# 1-Controller.net
KiCad netlist of a schematic drawn in Altium Designer
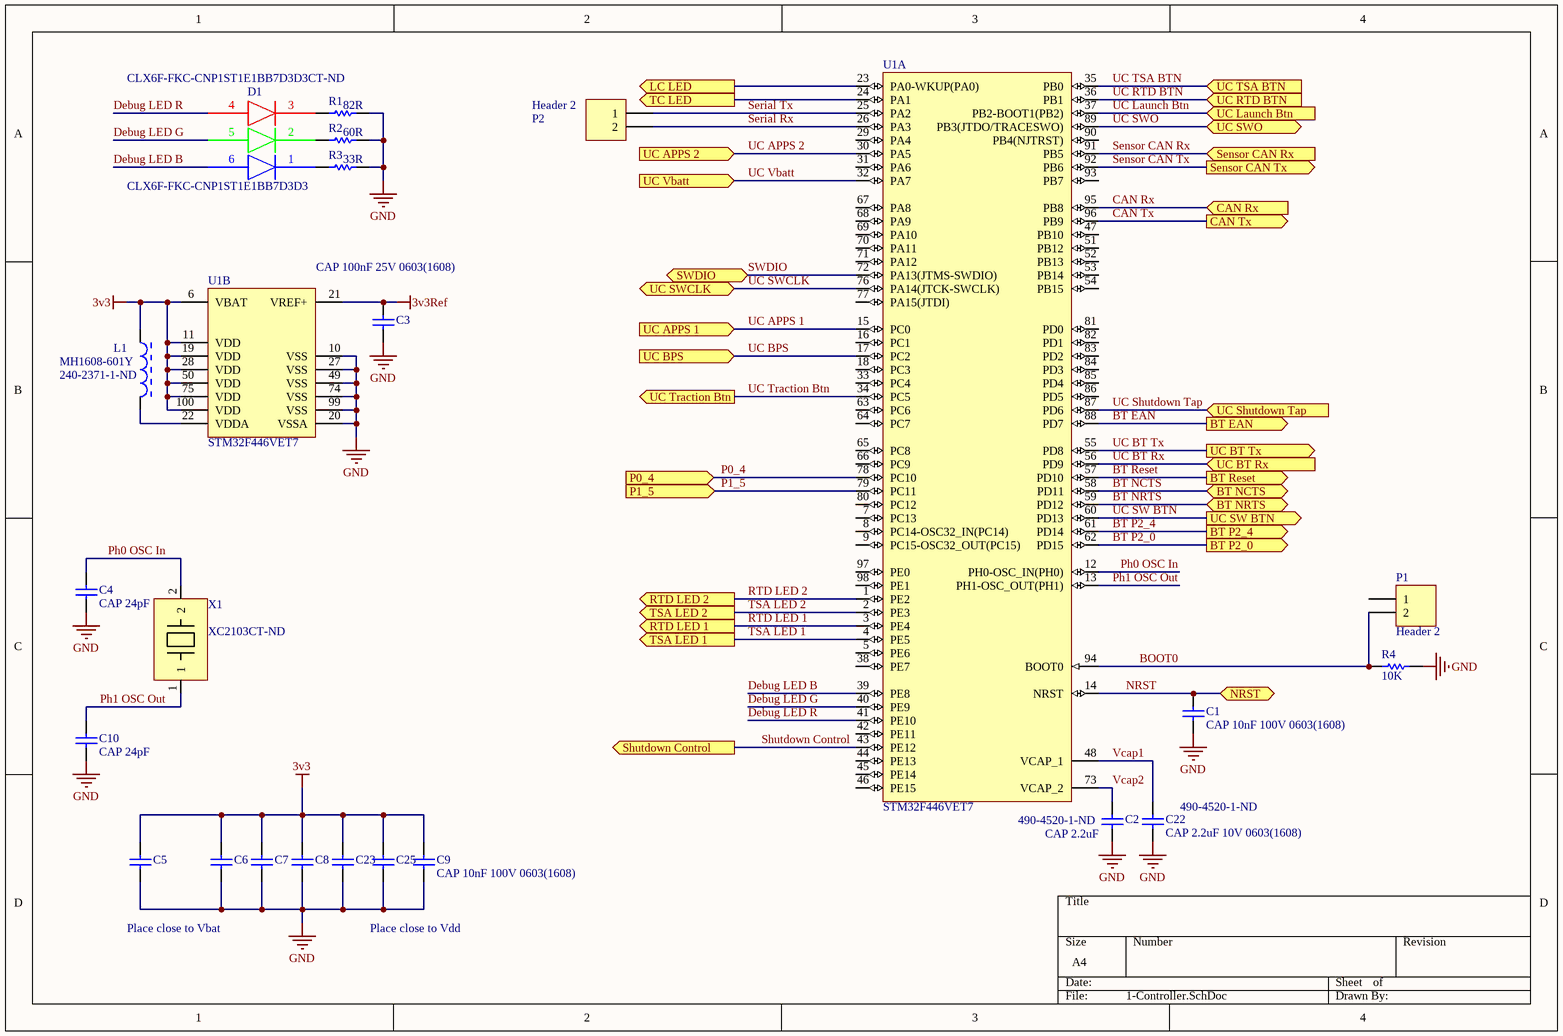
[diagram p0: 1-Controller.SchDoc]

(export (version "E")
  (design (tool "Eeschema 10.0.6"))
  (components
    (comp (ref "C1")
      (value "CAP 10nF 100V 0603(1608)")
      (footprint "CAPC0603(1608)100_M")
      (description "CAP 10nF 100V ±20% 0603 (1608 Metric) Thickness 1mm SMD")
      (fields (field (name "TOLERANCE") "Â±20%"))
      (libsource (lib "Altium Content Vault") (part "CAP"))
    )
    (comp (ref "C2")
      (value "CAP 2.2uF")
      (footprint "CAPC0603(1608)55_N")
      (description "CAP 2.2uF 10V ±10% 0603 (1608 Metric) Thickness 0.55mm SMD")
      (fields (field (name "TOLERANCE") "Â±10%") (field (name "SUPPLIER PART NUMBER 1") "490-4520-1-ND"))
      (libsource (lib "Altium Content Vault") (part "CAP"))
    )
    (comp (ref "C3")
      (value "CAP 100nF 25V 0603(1608)")
      (footprint "CAPC0603(1608)100_N")
      (description "CAP 100nF 25V ±20% 0603 (1608 Metric) Thickness 1mm SMD")
      (fields (field (name "TOLERANCE") "Â±20%"))
      (libsource (lib "Altium Content Vault") (part "CAP"))
    )
    (comp (ref "C4")
      (value "CAP 24pF")
      (footprint "CAPC0603(1608)100_N")
      (description "CAP 24pF 16V ±2% 0603 (1608 Metric) Thickness 1mm SMD")
      (fields (field (name "TOLERANCE") "Â±2%"))
      (libsource (lib "Altium Content Vault") (part "CAP"))
    )
    (comp (ref "C5")
      (value "CAP 10nF 100V 0603(1608)")
      (footprint "CAPC0603(1608)100_M")
      (description "CAP 10nF 100V ±20% 0603 (1608 Metric) Thickness 1mm SMD")
      (fields (field (name "TOLERANCE") "Â±20%"))
      (libsource (lib "Altium Content Vault") (part "CAP"))
    )
    (comp (ref "C6")
      (value "CAP 10nF 100V 0603(1608)")
      (footprint "CAPC0603(1608)100_M")
      (description "CAP 10nF 100V ±20% 0603 (1608 Metric) Thickness 1mm SMD")
      (fields (field (name "TOLERANCE") "Â±20%"))
      (libsource (lib "Altium Content Vault") (part "CAP"))
    )
    (comp (ref "C7")
      (value "CAP 10nF 100V 0603(1608)")
      (footprint "CAPC0603(1608)100_M")
      (description "CAP 10nF 100V ±20% 0603 (1608 Metric) Thickness 1mm SMD")
      (fields (field (name "TOLERANCE") "Â±20%"))
      (libsource (lib "Altium Content Vault") (part "CAP"))
    )
    (comp (ref "C8")
      (value "CAP 10nF 100V 0603(1608)")
      (footprint "CAPC0603(1608)100_M")
      (description "CAP 10nF 100V ±20% 0603 (1608 Metric) Thickness 1mm SMD")
      (fields (field (name "TOLERANCE") "Â±20%"))
      (libsource (lib "Altium Content Vault") (part "CAP"))
    )
    (comp (ref "C9")
      (value "CAP 10nF 100V 0603(1608)")
      (footprint "CAPC0603(1608)100_M")
      (description "CAP 10nF 100V ±20% 0603 (1608 Metric) Thickness 1mm SMD")
      (fields (field (name "TOLERANCE") "Â±20%"))
      (libsource (lib "Altium Content Vault") (part "CAP"))
    )
    (comp (ref "C10")
      (value "CAP 24pF")
      (footprint "CAPC0603(1608)100_N")
      (description "CAP 24pF 16V ±2% 0603 (1608 Metric) Thickness 1mm SMD")
      (fields (field (name "TOLERANCE") "Â±2%"))
      (libsource (lib "Altium Content Vault") (part "CAP"))
    )
    (comp (ref "C22")
      (value "CAP 2.2uF 10V 0603(1608)")
      (footprint "CAPC0603(1608)55_N")
      (description "CAP 2.2uF 10V ±10% 0603 (1608 Metric) Thickness 0.55mm SMD")
      (fields (field (name "TOLERANCE") "Â±10%") (field (name "SUPPLIER PART NUMBER 1") "490-4520-1-ND"))
      (libsource (lib "Altium Content Vault") (part "CAP"))
    )
    (comp (ref "C23")
      (value "CAP 10nF 100V 0603(1608)")
      (footprint "CAPC0603(1608)100_M")
      (description "CAP 10nF 100V ±20% 0603 (1608 Metric) Thickness 1mm SMD")
      (fields (field (name "TOLERANCE") "Â±20%"))
      (libsource (lib "Altium Content Vault") (part "CAP"))
    )
    (comp (ref "C25")
      (value "CAP 10nF 100V 0603(1608)")
      (footprint "CAPC0603(1608)100_M")
      (description "CAP 10nF 100V ±20% 0603 (1608 Metric) Thickness 1mm SMD")
      (fields (field (name "TOLERANCE") "Â±20%"))
      (libsource (lib "Altium Content Vault") (part "CAP"))
    )
    (comp (ref "D1")
      (value "CLX6F-FKC-CNP1ST1E1BB7D3D3")
      (footprint "CLX6C-FKB")
      (fields (field (name "SUPPLIER PART NUMBER 1") "CLX6F-FKC-CNP1ST1E1BB7D3D3CT-ND"))
      (libsource (lib "VCB_2019") (part "LED - CLX6F-FKC-CNP1ST1E1BB7D3D3"))
    )
    (comp (ref "L1")
      (value "MH1608-601Y")
      (footprint "BOUR-MH1608_V")
      (description "Chip Bead, 600 Ohm, 1 A, -55 to 125 degC, 2-Pin SMD (0603), RoHS, Tape and Reel")
      (fields (field (name "MANUFACTURER") "Bourns") (field (name "SUPPLIER PART NUMBER 1") "240-2371-1-ND"))
      (libsource (lib "Altium Content Vault") (part "IND-FB-2"))
    )
    (comp (ref "P1")
      (value "Header 2")
      (footprint "HDR1X2")
      (description "Header, 2-Pin")
      (fields (field (name "PUBLISHER") "Altium Limited"))
      (libsource (lib "") (part "Header 2_1"))
    )
    (comp (ref "P2")
      (value "Header 2")
      (footprint "HDR1X2")
      (description "Header, 2-Pin")
      (fields (field (name "PUBLISHER") "Altium Limited"))
      (libsource (lib "Miscellaneous Connectors") (part "Header 2"))
    )
    (comp (ref "R1")
      (value "82R")
      (footprint "RESC0603(1608)_N")
      (description "82R 0.1W 5% 0603 (1608 Metric)  SMD")
      (fields (field (name "TOLERANCE") "5 %") (field (name "POWER") "0.1 W"))
      (libsource (lib "Altium Content Vault") (part "RES"))
    )
    (comp (ref "R2")
      (value "60R")
      (footprint "RESC0603(1608)_N")
      (description "60R4 0.1W 1% 0603 (1608 Metric)  SMD")
      (fields (field (name "TOLERANCE") "1 %") (field (name "POWER") "0.1 W"))
      (libsource (lib "Altium Content Vault") (part "RES"))
    )
    (comp (ref "R3")
      (value "33R")
      (footprint "RESC0603(1608)_N")
      (description "33R 0.1W 5% 0603 (1608 Metric)  SMD")
      (fields (field (name "TOLERANCE") "5 %") (field (name "POWER") "0.1 W"))
      (libsource (lib "Altium Content Vault") (part "RES"))
    )
    (comp (ref "R4")
      (value "10K")
      (footprint "RESC0603(1608)_N")
      (description "10K 0.1W 5% 0603 (1608 Metric)  SMD")
      (fields (field (name "TOLERANCE") "5 %") (field (name "POWER") "0.1 W"))
      (libsource (lib "Altium Content Vault") (part "RES"))
    )
    (comp (ref "U1")
      (value "STM32F446VET7")
      (footprint "STM-LQFP100_L")
      (libsource (lib "Altium Content Vault") (part "MC-ARM-STM32F446-LQFP100"))
    )
    (comp (ref "X1")
      (value "7A-8.000MAAJ-T")
      (footprint "2-SMD, No Lead")
      (fields
        (field (name "MANUFACTURER") "TXC CORPORATION")
        (field (name "SUPPLIER PART NUMBER 1") "XC2103CT-ND")
      )
      (libsource (lib "VCU Library") (part "8MHz crystal, 7A-8.000MAAJ-T"))
    )
  )
  (nets
    (net (code "1") (name "/BOOT0") (class "Default")
      (node (ref "P1") (pin "2") (pinfunction "2_2") (pintype "passive"))
      (node (ref "R4") (pin "1") (pinfunction "1_1") (pintype "passive"))
      (node (ref "U1") (pin "94") (pinfunction "BOOT0_94") (pintype "input"))
    )
    (net (code "2") (name "/BT EAN") (class "Default")
      (node (ref "U1") (pin "88") (pinfunction "PD7_88") (pintype "bidirectional"))
    )
    (net (code "3") (name "/BT NCTS") (class "Default")
      (node (ref "U1") (pin "58") (pinfunction "PD11_58") (pintype "bidirectional"))
    )
    (net (code "4") (name "/BT NRTS") (class "Default")
      (node (ref "U1") (pin "59") (pinfunction "PD12_59") (pintype "bidirectional"))
    )
    (net (code "5") (name "/BT P2_0") (class "Default")
      (node (ref "U1") (pin "62") (pinfunction "PD15_62") (pintype "bidirectional"))
    )
    (net (code "6") (name "/BT P2_4") (class "Default")
      (node (ref "U1") (pin "61") (pinfunction "PD14_61") (pintype "bidirectional"))
    )
    (net (code "7") (name "/BT Reset") (class "Default")
      (node (ref "U1") (pin "57") (pinfunction "PD10_57") (pintype "bidirectional"))
    )
    (net (code "8") (name "/CAN Rx") (class "Default")
      (node (ref "U1") (pin "95") (pinfunction "PB8_95") (pintype "bidirectional"))
    )
    (net (code "9") (name "/CAN Tx") (class "Default")
      (node (ref "U1") (pin "96") (pinfunction "PB9_96") (pintype "bidirectional"))
    )
    (net (code "10") (name "/Debug LED B") (class "Default")
      (node (ref "D1") (pin "6") (pinfunction "B_6") (pintype "passive"))
      (node (ref "U1") (pin "39") (pinfunction "PE8_39") (pintype "bidirectional"))
    )
    (net (code "11") (name "/Debug LED G") (class "Default")
      (node (ref "D1") (pin "5") (pinfunction "G_5") (pintype "passive"))
      (node (ref "U1") (pin "40") (pinfunction "PE9_40") (pintype "bidirectional"))
    )
    (net (code "12") (name "/Debug LED R") (class "Default")
      (node (ref "D1") (pin "4") (pinfunction "R_4") (pintype "passive"))
      (node (ref "U1") (pin "41") (pinfunction "PE10_41") (pintype "bidirectional"))
    )
    (net (code "13") (name "/LC LED") (class "Default")
      (node (ref "U1") (pin "23") (pinfunction "PA0-WKUP(PA0)_23") (pintype "bidirectional"))
    )
    (net (code "14") (name "/NRST") (class "Default")
      (node (ref "C1") (pin "2") (pinfunction "2_2") (pintype "passive"))
      (node (ref "U1") (pin "14") (pinfunction "NRST_14") (pintype "bidirectional"))
    )
    (net (code "15") (name "/P0_4") (class "Default")
      (node (ref "U1") (pin "78") (pinfunction "PC10_78") (pintype "bidirectional"))
    )
    (net (code "16") (name "/P1_5") (class "Default")
      (node (ref "U1") (pin "79") (pinfunction "PC11_79") (pintype "bidirectional"))
    )
    (net (code "17") (name "/Ph0 OSC In") (class "Default")
      (node (ref "C4") (pin "2") (pinfunction "2_2") (pintype "passive"))
      (node (ref "U1") (pin "12") (pinfunction "PH0-OSC_IN(PH0)_12") (pintype "bidirectional"))
      (node (ref "X1") (pin "2") (pinfunction "2_2") (pintype "passive"))
    )
    (net (code "18") (name "/Ph1 OSC Out") (class "Default")
      (node (ref "C10") (pin "2") (pinfunction "2_2") (pintype "passive"))
      (node (ref "U1") (pin "13") (pinfunction "PH1-OSC_OUT(PH1)_13") (pintype "bidirectional"))
      (node (ref "X1") (pin "1") (pinfunction "1_1") (pintype "passive"))
    )
    (net (code "19") (name "/RTD LED 1") (class "Default")
      (node (ref "U1") (pin "3") (pinfunction "PE4_3") (pintype "bidirectional"))
    )
    (net (code "20") (name "/RTD LED 2") (class "Default")
      (node (ref "U1") (pin "1") (pinfunction "PE2_1") (pintype "bidirectional"))
    )
    (net (code "21") (name "/SWDIO") (class "Default")
      (node (ref "U1") (pin "72") (pinfunction "PA13(JTMS-SWDIO)_72") (pintype "bidirectional"))
    )
    (net (code "22") (name "/Sensor CAN Rx") (class "Default")
      (node (ref "U1") (pin "91") (pinfunction "PB5_91") (pintype "bidirectional"))
    )
    (net (code "23") (name "/Sensor CAN Tx") (class "Default")
      (node (ref "U1") (pin "92") (pinfunction "PB6_92") (pintype "bidirectional"))
    )
    (net (code "24") (name "/Serial Rx") (class "Default")
      (node (ref "P2") (pin "2") (pinfunction "2_2") (pintype "passive"))
      (node (ref "U1") (pin "26") (pinfunction "PA3_26") (pintype "bidirectional"))
    )
    (net (code "25") (name "/Serial Tx") (class "Default")
      (node (ref "P2") (pin "1") (pinfunction "1_1") (pintype "passive"))
      (node (ref "U1") (pin "25") (pinfunction "PA2_25") (pintype "bidirectional"))
    )
    (net (code "26") (name "/Shutdown Control") (class "Default")
      (node (ref "U1") (pin "43") (pinfunction "PE12_43") (pintype "bidirectional"))
    )
    (net (code "27") (name "/TC LED") (class "Default")
      (node (ref "U1") (pin "24") (pinfunction "PA1_24") (pintype "bidirectional"))
    )
    (net (code "28") (name "/TSA LED 1") (class "Default")
      (node (ref "U1") (pin "4") (pinfunction "PE5_4") (pintype "bidirectional"))
    )
    (net (code "29") (name "/TSA LED 2") (class "Default")
      (node (ref "U1") (pin "2") (pinfunction "PE3_2") (pintype "bidirectional"))
    )
    (net (code "30") (name "/UC APPS 1") (class "Default")
      (node (ref "U1") (pin "15") (pinfunction "PC0_15") (pintype "bidirectional"))
    )
    (net (code "31") (name "/UC APPS 2") (class "Default")
      (node (ref "U1") (pin "30") (pinfunction "PA5_30") (pintype "bidirectional"))
    )
    (net (code "32") (name "/UC BPS") (class "Default")
      (node (ref "U1") (pin "17") (pinfunction "PC2_17") (pintype "bidirectional"))
    )
    (net (code "33") (name "/UC BT Rx") (class "Default")
      (node (ref "U1") (pin "56") (pinfunction "PD9_56") (pintype "bidirectional"))
    )
    (net (code "34") (name "/UC BT Tx") (class "Default")
      (node (ref "U1") (pin "55") (pinfunction "PD8_55") (pintype "bidirectional"))
    )
    (net (code "35") (name "/UC Launch Btn") (class "Default")
      (node (ref "U1") (pin "37") (pinfunction "PB2-BOOT1(PB2)_37") (pintype "bidirectional"))
    )
    (net (code "36") (name "/UC RTD BTN") (class "Default")
      (node (ref "U1") (pin "36") (pinfunction "PB1_36") (pintype "bidirectional"))
    )
    (net (code "37") (name "/UC SW BTN") (class "Default")
      (node (ref "U1") (pin "60") (pinfunction "PD13_60") (pintype "bidirectional"))
    )
    (net (code "38") (name "/UC SWCLK") (class "Default")
      (node (ref "U1") (pin "76") (pinfunction "PA14(JTCK-SWCLK)_76") (pintype "bidirectional"))
    )
    (net (code "39") (name "/UC SWO") (class "Default")
      (node (ref "U1") (pin "89") (pinfunction "PB3(JTDO/TRACESWO)_89") (pintype "bidirectional"))
    )
    (net (code "40") (name "/UC Shutdown Tap") (class "Default")
      (node (ref "U1") (pin "87") (pinfunction "PD6_87") (pintype "bidirectional"))
    )
    (net (code "41") (name "/UC TSA BTN") (class "Default")
      (node (ref "U1") (pin "35") (pinfunction "PB0_35") (pintype "bidirectional"))
    )
    (net (code "42") (name "/UC Traction Btn") (class "Default")
      (node (ref "U1") (pin "34") (pinfunction "PC5_34") (pintype "bidirectional"))
    )
    (net (code "43") (name "/UC Vbatt") (class "Default")
      (node (ref "U1") (pin "32") (pinfunction "PA7_32") (pintype "bidirectional"))
    )
    (net (code "44") (name "/Vcap1") (class "Default")
      (node (ref "C22") (pin "2") (pinfunction "2_2") (pintype "passive"))
      (node (ref "U1") (pin "48") (pinfunction "VCAP_1_48") (pintype "passive"))
    )
    (net (code "45") (name "/Vcap2") (class "Default")
      (node (ref "C2") (pin "2") (pinfunction "2_2") (pintype "passive"))
      (node (ref "U1") (pin "73") (pinfunction "VCAP_2_73") (pintype "passive"))
    )
    (net (code "46") (name "3v3") (class "Default")
      (node (ref "C23") (pin "2") (pinfunction "2_2") (pintype "passive"))
      (node (ref "C25") (pin "2") (pinfunction "2_2") (pintype "passive"))
      (node (ref "C5") (pin "2") (pinfunction "2_2") (pintype "passive"))
      (node (ref "C6") (pin "2") (pinfunction "2_2") (pintype "passive"))
      (node (ref "C7") (pin "2") (pinfunction "2_2") (pintype "passive"))
      (node (ref "C8") (pin "2") (pinfunction "2_2") (pintype "passive"))
      (node (ref "C9") (pin "2") (pinfunction "2_2") (pintype "passive"))
      (node (ref "L1") (pin "1") (pinfunction "1_1") (pintype "passive"))
      (node (ref "U1") (pin "100") (pinfunction "VDD_100") (pintype "power_in"))
      (node (ref "U1") (pin "11") (pinfunction "VDD_11") (pintype "power_in"))
      (node (ref "U1") (pin "19") (pinfunction "VDD_19") (pintype "power_in"))
      (node (ref "U1") (pin "28") (pinfunction "VDD_28") (pintype "power_in"))
      (node (ref "U1") (pin "50") (pinfunction "VDD_50") (pintype "power_in"))
      (node (ref "U1") (pin "6") (pinfunction "VBAT_6") (pintype "power_in"))
      (node (ref "U1") (pin "75") (pinfunction "VDD_75") (pintype "power_in"))
    )
    (net (code "47") (name "3v3Ref") (class "Default")
      (node (ref "C3") (pin "2") (pinfunction "2_2") (pintype "passive"))
      (node (ref "U1") (pin "21") (pinfunction "VREF+_21") (pintype "power_in"))
    )
    (net (code "48") (name "GND") (class "Default")
      (node (ref "C1") (pin "1") (pinfunction "1_1") (pintype "passive"))
      (node (ref "C10") (pin "1") (pinfunction "1_1") (pintype "passive"))
      (node (ref "C2") (pin "1") (pinfunction "1_1") (pintype "passive"))
      (node (ref "C22") (pin "1") (pinfunction "1_1") (pintype "passive"))
      (node (ref "C23") (pin "1") (pinfunction "1_1") (pintype "passive"))
      (node (ref "C25") (pin "1") (pinfunction "1_1") (pintype "passive"))
      (node (ref "C3") (pin "1") (pinfunction "1_1") (pintype "passive"))
      (node (ref "C4") (pin "1") (pinfunction "1_1") (pintype "passive"))
      (node (ref "C5") (pin "1") (pinfunction "1_1") (pintype "passive"))
      (node (ref "C6") (pin "1") (pinfunction "1_1") (pintype "passive"))
      (node (ref "C7") (pin "1") (pinfunction "1_1") (pintype "passive"))
      (node (ref "C8") (pin "1") (pinfunction "1_1") (pintype "passive"))
      (node (ref "C9") (pin "1") (pinfunction "1_1") (pintype "passive"))
      (node (ref "R1") (pin "2") (pinfunction "2_2") (pintype "passive"))
      (node (ref "R2") (pin "2") (pinfunction "2_2") (pintype "passive"))
      (node (ref "R3") (pin "2") (pinfunction "2_2") (pintype "passive"))
      (node (ref "R4") (pin "2") (pinfunction "2_2") (pintype "passive"))
      (node (ref "U1") (pin "10") (pinfunction "VSS_10") (pintype "power_in"))
      (node (ref "U1") (pin "20") (pinfunction "VSSA_20") (pintype "power_in"))
      (node (ref "U1") (pin "27") (pinfunction "VSS_27") (pintype "power_in"))
      (node (ref "U1") (pin "49") (pinfunction "VSS_49") (pintype "power_in"))
      (node (ref "U1") (pin "74") (pinfunction "VSS_74") (pintype "power_in"))
      (node (ref "U1") (pin "99") (pinfunction "VSS_99") (pintype "power_in"))
    )
    (net (code "49") (name "Net-(D1-B-Pad1)") (class "Default")
      (node (ref "D1") (pin "1") (pinfunction "B_1") (pintype "passive"))
      (node (ref "R3") (pin "1") (pinfunction "1_1") (pintype "passive"))
    )
    (net (code "50") (name "Net-(D1-G-Pad2)") (class "Default")
      (node (ref "D1") (pin "2") (pinfunction "G_2") (pintype "passive"))
      (node (ref "R2") (pin "1") (pinfunction "1_1") (pintype "passive"))
    )
    (net (code "51") (name "Net-(D1-R-Pad3)") (class "Default")
      (node (ref "D1") (pin "3") (pinfunction "R_3") (pintype "passive"))
      (node (ref "R1") (pin "1") (pinfunction "1_1") (pintype "passive"))
    )
    (net (code "52") (name "Net-(U1B-VDDA)") (class "Default")
      (node (ref "L1") (pin "2") (pinfunction "2_2") (pintype "passive"))
      (node (ref "U1") (pin "22") (pinfunction "VDDA_22") (pintype "power_in"))
    )
    (net (code "53") (name "unconnected-(P1-Pad1)") (class "Default")
      (node (ref "P1") (pin "1") (pinfunction "1_1") (pintype "passive"))
    )
    (net (code "54") (name "unconnected-(U1A-PA4-Pad29)") (class "Default")
      (node (ref "U1") (pin "29") (pinfunction "PA4_29") (pintype "bidirectional"))
    )
    (net (code "55") (name "unconnected-(U1A-PA6-Pad31)") (class "Default")
      (node (ref "U1") (pin "31") (pinfunction "PA6_31") (pintype "bidirectional"))
    )
    (net (code "56") (name "unconnected-(U1A-PA8-Pad67)") (class "Default")
      (node (ref "U1") (pin "67") (pinfunction "PA8_67") (pintype "bidirectional"))
    )
    (net (code "57") (name "unconnected-(U1A-PA9-Pad68)") (class "Default")
      (node (ref "U1") (pin "68") (pinfunction "PA9_68") (pintype "bidirectional"))
    )
    (net (code "58") (name "unconnected-(U1A-PA10-Pad69)") (class "Default")
      (node (ref "U1") (pin "69") (pinfunction "PA10_69") (pintype "bidirectional"))
    )
    (net (code "59") (name "unconnected-(U1A-PA11-Pad70)") (class "Default")
      (node (ref "U1") (pin "70") (pinfunction "PA11_70") (pintype "bidirectional"))
    )
    (net (code "60") (name "unconnected-(U1A-PA12-Pad71)") (class "Default")
      (node (ref "U1") (pin "71") (pinfunction "PA12_71") (pintype "bidirectional"))
    )
    (net (code "61") (name "unconnected-(U1A-PA15(JTDI)-Pad77)") (class "Default")
      (node (ref "U1") (pin "77") (pinfunction "PA15(JTDI)_77") (pintype "bidirectional"))
    )
    (net (code "62") (name "unconnected-(U1A-PB4(NJTRST)-Pad90)") (class "Default")
      (node (ref "U1") (pin "90") (pinfunction "PB4(NJTRST)_90") (pintype "bidirectional"))
    )
    (net (code "63") (name "unconnected-(U1A-PB7-Pad93)") (class "Default")
      (node (ref "U1") (pin "93") (pinfunction "PB7_93") (pintype "bidirectional"))
    )
    (net (code "64") (name "unconnected-(U1A-PB10-Pad47)") (class "Default")
      (node (ref "U1") (pin "47") (pinfunction "PB10_47") (pintype "bidirectional"))
    )
    (net (code "65") (name "unconnected-(U1A-PB12-Pad51)") (class "Default")
      (node (ref "U1") (pin "51") (pinfunction "PB12_51") (pintype "bidirectional"))
    )
    (net (code "66") (name "unconnected-(U1A-PB13-Pad52)") (class "Default")
      (node (ref "U1") (pin "52") (pinfunction "PB13_52") (pintype "bidirectional"))
    )
    (net (code "67") (name "unconnected-(U1A-PB14-Pad53)") (class "Default")
      (node (ref "U1") (pin "53") (pinfunction "PB14_53") (pintype "bidirectional"))
    )
    (net (code "68") (name "unconnected-(U1A-PB15-Pad54)") (class "Default")
      (node (ref "U1") (pin "54") (pinfunction "PB15_54") (pintype "bidirectional"))
    )
    (net (code "69") (name "unconnected-(U1A-PC1-Pad16)") (class "Default")
      (node (ref "U1") (pin "16") (pinfunction "PC1_16") (pintype "bidirectional"))
    )
    (net (code "70") (name "unconnected-(U1A-PC3-Pad18)") (class "Default")
      (node (ref "U1") (pin "18") (pinfunction "PC3_18") (pintype "bidirectional"))
    )
    (net (code "71") (name "unconnected-(U1A-PC4-Pad33)") (class "Default")
      (node (ref "U1") (pin "33") (pinfunction "PC4_33") (pintype "bidirectional"))
    )
    (net (code "72") (name "unconnected-(U1A-PC6-Pad63)") (class "Default")
      (node (ref "U1") (pin "63") (pinfunction "PC6_63") (pintype "bidirectional"))
    )
    (net (code "73") (name "unconnected-(U1A-PC7-Pad64)") (class "Default")
      (node (ref "U1") (pin "64") (pinfunction "PC7_64") (pintype "bidirectional"))
    )
    (net (code "74") (name "unconnected-(U1A-PC8-Pad65)") (class "Default")
      (node (ref "U1") (pin "65") (pinfunction "PC8_65") (pintype "bidirectional"))
    )
    (net (code "75") (name "unconnected-(U1A-PC9-Pad66)") (class "Default")
      (node (ref "U1") (pin "66") (pinfunction "PC9_66") (pintype "bidirectional"))
    )
    (net (code "76") (name "unconnected-(U1A-PC12-Pad80)") (class "Default")
      (node (ref "U1") (pin "80") (pinfunction "PC12_80") (pintype "bidirectional"))
    )
    (net (code "77") (name "unconnected-(U1A-PC13-Pad7)") (class "Default")
      (node (ref "U1") (pin "7") (pinfunction "PC13_7") (pintype "bidirectional"))
    )
    (net (code "78") (name "unconnected-(U1A-PC14-OSC32_IN(PC14)-Pad8)") (class "Default")
      (node (ref "U1") (pin "8") (pinfunction "PC14-OSC32_IN(PC14)_8") (pintype "bidirectional"))
    )
    (net (code "79") (name "unconnected-(U1A-PC15-OSC32_OUT(PC15)-Pad9)") (class "Default")
      (node (ref "U1") (pin "9") (pinfunction "PC15-OSC32_OUT(PC15)_9") (pintype "bidirectional"))
    )
    (net (code "80") (name "unconnected-(U1A-PD0-Pad81)") (class "Default")
      (node (ref "U1") (pin "81") (pinfunction "PD0_81") (pintype "bidirectional"))
    )
    (net (code "81") (name "unconnected-(U1A-PD1-Pad82)") (class "Default")
      (node (ref "U1") (pin "82") (pinfunction "PD1_82") (pintype "bidirectional"))
    )
    (net (code "82") (name "unconnected-(U1A-PD2-Pad83)") (class "Default")
      (node (ref "U1") (pin "83") (pinfunction "PD2_83") (pintype "bidirectional"))
    )
    (net (code "83") (name "unconnected-(U1A-PD3-Pad84)") (class "Default")
      (node (ref "U1") (pin "84") (pinfunction "PD3_84") (pintype "bidirectional"))
    )
    (net (code "84") (name "unconnected-(U1A-PD4-Pad85)") (class "Default")
      (node (ref "U1") (pin "85") (pinfunction "PD4_85") (pintype "bidirectional"))
    )
    (net (code "85") (name "unconnected-(U1A-PD5-Pad86)") (class "Default")
      (node (ref "U1") (pin "86") (pinfunction "PD5_86") (pintype "bidirectional"))
    )
    (net (code "86") (name "unconnected-(U1A-PE0-Pad97)") (class "Default")
      (node (ref "U1") (pin "97") (pinfunction "PE0_97") (pintype "bidirectional"))
    )
    (net (code "87") (name "unconnected-(U1A-PE1-Pad98)") (class "Default")
      (node (ref "U1") (pin "98") (pinfunction "PE1_98") (pintype "bidirectional"))
    )
    (net (code "88") (name "unconnected-(U1A-PE6-Pad5)") (class "Default")
      (node (ref "U1") (pin "5") (pinfunction "PE6_5") (pintype "bidirectional"))
    )
    (net (code "89") (name "unconnected-(U1A-PE7-Pad38)") (class "Default")
      (node (ref "U1") (pin "38") (pinfunction "PE7_38") (pintype "bidirectional"))
    )
    (net (code "90") (name "unconnected-(U1A-PE11-Pad42)") (class "Default")
      (node (ref "U1") (pin "42") (pinfunction "PE11_42") (pintype "bidirectional"))
    )
    (net (code "91") (name "unconnected-(U1A-PE13-Pad44)") (class "Default")
      (node (ref "U1") (pin "44") (pinfunction "PE13_44") (pintype "bidirectional"))
    )
    (net (code "92") (name "unconnected-(U1A-PE14-Pad45)") (class "Default")
      (node (ref "U1") (pin "45") (pinfunction "PE14_45") (pintype "bidirectional"))
    )
    (net (code "93") (name "unconnected-(U1A-PE15-Pad46)") (class "Default")
      (node (ref "U1") (pin "46") (pinfunction "PE15_46") (pintype "bidirectional"))
    )
  )
)
